# MaTouch_ESP32-S3_2_13_Quad-Color_Eink_V1.net
KiCad netlist of a schematic drawn in EAGLE
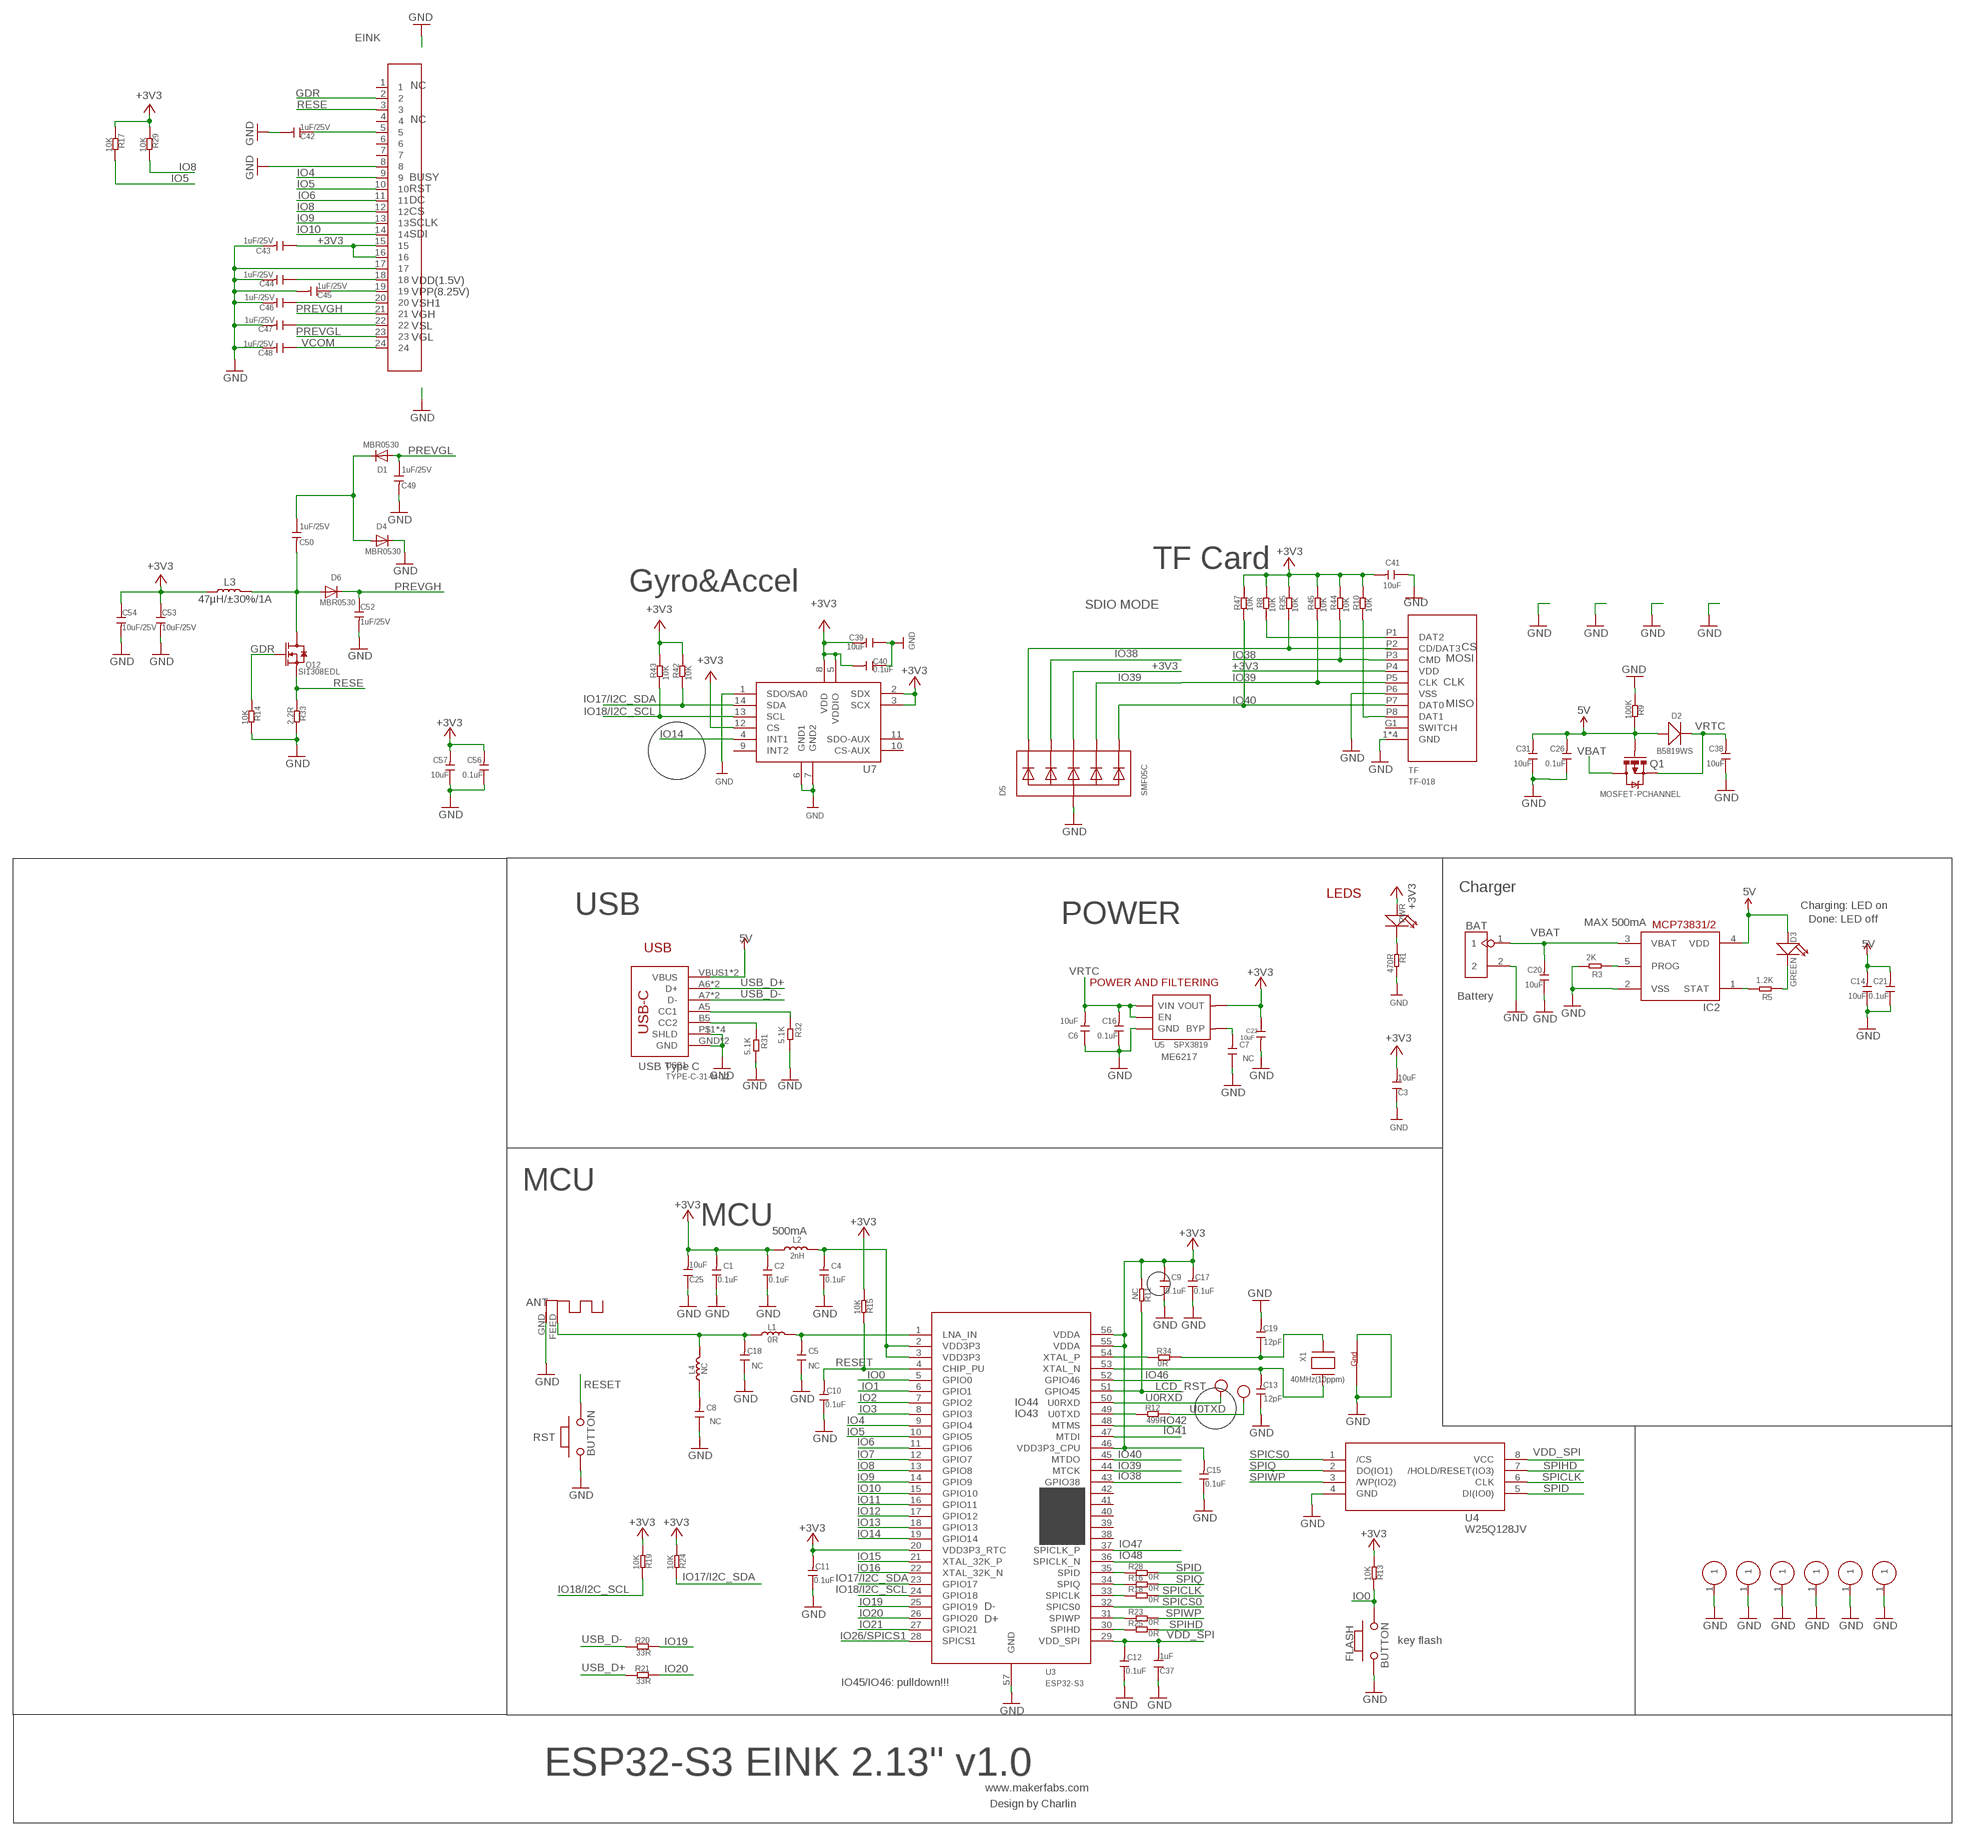
[diagram p0: schematic, sheet 1]

(export (version "E")
  (design (tool "Eeschema 10.0.6"))
  (components
    (comp (ref "ANT1")
      (value "ANTENNA")
      (footprint "eagle-import:RN-ANT")
      (libsource (lib "eagle-import") (part "ANTENNA"))
    )
    (comp (ref "BAT")
      (value "HEADER-2P-2.0")
      (footprint "eagle-import:2P-2.0")
      (libsource (lib "eagle-import") (part "HEADER-2P-2.0"))
    )
    (comp (ref "C1")
      (value "0.1uF")
      (footprint "eagle-import:DISCRETE_C0402")
      (libsource (lib "eagle-import") (part "DISCRETE_C-0402"))
    )
    (comp (ref "C2")
      (value "0.1uF")
      (footprint "eagle-import:DISCRETE_C0402")
      (libsource (lib "eagle-import") (part "DISCRETE_C-0402"))
    )
    (comp (ref "C3")
      (value "10uF")
      (footprint "eagle-import:DISCRETE_C0603")
      (libsource (lib "eagle-import") (part "DISCRETE_C-0603"))
    )
    (comp (ref "C4")
      (value "0.1uF")
      (footprint "eagle-import:DISCRETE_C0402")
      (libsource (lib "eagle-import") (part "DISCRETE_C-0402"))
    )
    (comp (ref "C5")
      (value "NC")
      (footprint "eagle-import:DISCRETE_C0402")
      (libsource (lib "eagle-import") (part "DISCRETE_C-0402"))
    )
    (comp (ref "C6")
      (value "10uF")
      (footprint "eagle-import:DISCRETE_C0603")
      (libsource (lib "eagle-import") (part "DISCRETE_C-0603"))
    )
    (comp (ref "C7")
      (value "NC")
      (footprint "eagle-import:DISCRETE_C0402")
      (libsource (lib "eagle-import") (part "DISCRETE_C-0402"))
    )
    (comp (ref "C8")
      (value "NC")
      (footprint "eagle-import:DISCRETE_C0402")
      (libsource (lib "eagle-import") (part "DISCRETE_C-0402"))
    )
    (comp (ref "C9")
      (value "0.1uF")
      (footprint "eagle-import:DISCRETE_C0402")
      (libsource (lib "eagle-import") (part "DISCRETE_C-0402"))
    )
    (comp (ref "C10")
      (value "0.1uF")
      (footprint "eagle-import:DISCRETE_C0402")
      (libsource (lib "eagle-import") (part "DISCRETE_C-0402"))
    )
    (comp (ref "C11")
      (value "0.1uF")
      (footprint "eagle-import:DISCRETE_C0402")
      (libsource (lib "eagle-import") (part "DISCRETE_C-0402"))
    )
    (comp (ref "C12")
      (value "0.1uF")
      (footprint "eagle-import:DISCRETE_C0402")
      (libsource (lib "eagle-import") (part "DISCRETE_C-0402"))
    )
    (comp (ref "C13")
      (value "12pF")
      (footprint "eagle-import:DISCRETE_C0402")
      (libsource (lib "eagle-import") (part "DISCRETE_C-0402"))
    )
    (comp (ref "C14")
      (value "10uF")
      (footprint "eagle-import:DISCRETE_C0402")
      (libsource (lib "eagle-import") (part "DISCRETE_C-0402"))
    )
    (comp (ref "C15")
      (value "0.1uF")
      (footprint "eagle-import:DISCRETE_C0402")
      (libsource (lib "eagle-import") (part "DISCRETE_C-0402"))
    )
    (comp (ref "C16")
      (value "0.1uF")
      (footprint "eagle-import:DISCRETE_C0402")
      (libsource (lib "eagle-import") (part "DISCRETE_C-0402"))
    )
    (comp (ref "C17")
      (value "0.1uF")
      (footprint "eagle-import:DISCRETE_C0402")
      (libsource (lib "eagle-import") (part "DISCRETE_C-0402"))
    )
    (comp (ref "C18")
      (value "NC")
      (footprint "eagle-import:DISCRETE_C0402")
      (libsource (lib "eagle-import") (part "DISCRETE_C-0402"))
    )
    (comp (ref "C19")
      (value "12pF")
      (footprint "eagle-import:DISCRETE_C0402")
      (libsource (lib "eagle-import") (part "DISCRETE_C-0402"))
    )
    (comp (ref "C20")
      (value "10uF")
      (footprint "eagle-import:DISCRETE_C0402")
      (libsource (lib "eagle-import") (part "DISCRETE_C-0402"))
    )
    (comp (ref "C21")
      (value "0.1uF")
      (footprint "eagle-import:DISCRETE_C0402")
      (libsource (lib "eagle-import") (part "DISCRETE_C-0402"))
    )
    (comp (ref "C22")
      (value "10uF")
      (footprint "eagle-import:0603")
      (libsource (lib "eagle-import") (part "C-0603"))
    )
    (comp (ref "C25")
      (value "10uF")
      (footprint "eagle-import:DISCRETE_C0603")
      (libsource (lib "eagle-import") (part "DISCRETE_C-0603"))
    )
    (comp (ref "C26")
      (value "0.1uF")
      (footprint "eagle-import:DISCRETE_C0402")
      (libsource (lib "eagle-import") (part "DISCRETE_C-0402"))
    )
    (comp (ref "C31")
      (value "10uF")
      (footprint "eagle-import:DISCRETE_C0402")
      (libsource (lib "eagle-import") (part "DISCRETE_C-0402"))
    )
    (comp (ref "C37")
      (value "1uF")
      (footprint "eagle-import:DISCRETE_C0603")
      (libsource (lib "eagle-import") (part "DISCRETE_C-0603"))
    )
    (comp (ref "C38")
      (value "10uF")
      (footprint "eagle-import:DISCRETE_C0402")
      (libsource (lib "eagle-import") (part "DISCRETE_C-0402"))
    )
    (comp (ref "C39")
      (value "10uF")
      (footprint "eagle-import:DISCRETE_C0402")
      (libsource (lib "eagle-import") (part "DISCRETE_C-0402"))
    )
    (comp (ref "C40")
      (value "0.1uF")
      (footprint "eagle-import:DISCRETE_C0402")
      (libsource (lib "eagle-import") (part "DISCRETE_C-0402"))
    )
    (comp (ref "C41")
      (value "10uF")
      (footprint "eagle-import:DISCRETE_C0402")
      (libsource (lib "eagle-import") (part "DISCRETE_C-0402"))
    )
    (comp (ref "C42")
      (value "1uF/25V")
      (footprint "eagle-import:DISCRETE_C0402")
      (libsource (lib "eagle-import") (part "DISCRETE_C-0402"))
    )
    (comp (ref "C43")
      (value "1uF/25V")
      (footprint "eagle-import:DISCRETE_C0402")
      (libsource (lib "eagle-import") (part "DISCRETE_C-0402"))
    )
    (comp (ref "C44")
      (value "1uF/25V")
      (footprint "eagle-import:DISCRETE_C0402")
      (libsource (lib "eagle-import") (part "DISCRETE_C-0402"))
    )
    (comp (ref "C45")
      (value "1uF/25V")
      (footprint "eagle-import:DISCRETE_C0402")
      (libsource (lib "eagle-import") (part "DISCRETE_C-0402"))
    )
    (comp (ref "C46")
      (value "1uF/25V")
      (footprint "eagle-import:DISCRETE_C0402")
      (libsource (lib "eagle-import") (part "DISCRETE_C-0402"))
    )
    (comp (ref "C47")
      (value "1uF/25V")
      (footprint "eagle-import:DISCRETE_C0402")
      (libsource (lib "eagle-import") (part "DISCRETE_C-0402"))
    )
    (comp (ref "C48")
      (value "1uF/25V")
      (footprint "eagle-import:DISCRETE_C0402")
      (libsource (lib "eagle-import") (part "DISCRETE_C-0402"))
    )
    (comp (ref "C49")
      (value "1uF/25V")
      (footprint "eagle-import:DISCRETE_C0402")
      (libsource (lib "eagle-import") (part "DISCRETE_C-0402"))
    )
    (comp (ref "C50")
      (value "1uF/25V")
      (footprint "eagle-import:DISCRETE_C0402")
      (libsource (lib "eagle-import") (part "DISCRETE_C-0402"))
    )
    (comp (ref "C52")
      (value "1uF/25V")
      (footprint "eagle-import:0603")
      (libsource (lib "eagle-import") (part "C-0603"))
    )
    (comp (ref "C53")
      (value "10uF/25V")
      (footprint "eagle-import:0603")
      (libsource (lib "eagle-import") (part "C-0603"))
    )
    (comp (ref "C54")
      (value "10uF/25V")
      (footprint "eagle-import:0603")
      (libsource (lib "eagle-import") (part "C-0603"))
    )
    (comp (ref "C56")
      (value "0.1uF")
      (footprint "eagle-import:DISCRETE_C0402")
      (libsource (lib "eagle-import") (part "DISCRETE_C-0402"))
    )
    (comp (ref "C57")
      (value "10uF")
      (footprint "eagle-import:DISCRETE_C0402")
      (libsource (lib "eagle-import") (part "DISCRETE_C-0402"))
    )
    (comp (ref "D1")
      (value "MBR0530")
      (footprint "eagle-import:SOD-323F")
      (libsource (lib "eagle-import") (part "DIODESOD-323F"))
    )
    (comp (ref "D2")
      (value "B5819WS")
      (footprint "eagle-import:SOD323")
      (libsource (lib "eagle-import") (part "D'0805'"))
    )
    (comp (ref "D3")
      (value "GREEN")
      (footprint "eagle-import:DISCRETE_LED-0603")
      (libsource (lib "eagle-import") (part "DISCRETE_LED0603"))
    )
    (comp (ref "D4")
      (value "MBR0530")
      (footprint "eagle-import:SOD-323F")
      (libsource (lib "eagle-import") (part "DIODESOD-323F"))
    )
    (comp (ref "D5")
      (value "SMF05C")
      (footprint "eagle-import:SOT363")
      (libsource (lib "eagle-import") (part "TVSARRAY_5LANE"))
    )
    (comp (ref "D6")
      (value "MBR0530")
      (footprint "eagle-import:SOD-323F")
      (libsource (lib "eagle-import") (part "DIODESOD-323F"))
    )
    (comp (ref "FLASH")
      (value "BUTTON")
      (footprint "eagle-import:157SW")
      (libsource (lib "eagle-import") (part "PB157"))
    )
    (comp (ref "IC2")
      (value "TP4054")
      (footprint "eagle-import:SOT23-5L")
      (libsource (lib "eagle-import") (part "MCP73831/OT"))
    )
    (comp (ref "J1")
      (value "FPC24-80P-A")
      (footprint "eagle-import:SMD24-80P-1960L440W")
      (libsource (lib "eagle-import") (part "FPC24-80P-A"))
    )
    (comp (ref "L1")
      (value "0R")
      (footprint "eagle-import:DISCRETE_L0402")
      (libsource (lib "eagle-import") (part "DISCRETE_L0402"))
    )
    (comp (ref "L2")
      (value "2nH")
      (footprint "eagle-import:DISCRETE_L0603")
      (libsource (lib "eagle-import") (part "DISCRETE_L0603"))
    )
    (comp (ref "L3")
      (value "47µH/±30%/1A")
      (footprint "eagle-import:CR54")
      (fields (field (name "PROD_ID") "NDUC-10789"))
      (libsource (lib "eagle-import") (part "INDUCTOR-CR54-47UH"))
    )
    (comp (ref "L4")
      (value "NC")
      (footprint "eagle-import:DISCRETE_L0402")
      (libsource (lib "eagle-import") (part "DISCRETE_L0402"))
    )
    (comp (ref "PWR")
      (value "DISCRETE_LED0603")
      (footprint "eagle-import:DISCRETE_LED-0603")
      (libsource (lib "eagle-import") (part "DISCRETE_LED0603"))
    )
    (comp (ref "Q1")
      (value "MOSFET-PCHANNEL")
      (footprint "eagle-import:SOT23-3")
      (libsource (lib "eagle-import") (part "MOSFET-PCHANNEL"))
    )
    (comp (ref "Q12")
      (value "SI1308EDL")
      (footprint "eagle-import:SOT23")
      (libsource (lib "eagle-import") (part "MOSFET-N'SOT23'"))
    )
    (comp (ref "R1")
      (value "470R")
      (footprint "eagle-import:DISCRETE_R0402")
      (libsource (lib "eagle-import") (part "DISCRETE_R-0402"))
    )
    (comp (ref "R3")
      (value "2K")
      (footprint "eagle-import:DISCRETE_R0402")
      (libsource (lib "eagle-import") (part "DISCRETE_R-0402"))
    )
    (comp (ref "R5")
      (value "1.2K")
      (footprint "eagle-import:DISCRETE_R0402")
      (libsource (lib "eagle-import") (part "DISCRETE_R-0402"))
    )
    (comp (ref "R8")
      (value "10K")
      (footprint "eagle-import:DISCRETE_R0402")
      (libsource (lib "eagle-import") (part "DISCRETE_R-0402"))
    )
    (comp (ref "R9")
      (value "100K")
      (footprint "eagle-import:DISCRETE_R0402")
      (libsource (lib "eagle-import") (part "DISCRETE_R-0402"))
    )
    (comp (ref "R10")
      (value "10K")
      (footprint "eagle-import:DISCRETE_R0402")
      (libsource (lib "eagle-import") (part "DISCRETE_R-0402"))
    )
    (comp (ref "R11")
      (value "NC")
      (footprint "eagle-import:DISCRETE_R0402")
      (libsource (lib "eagle-import") (part "DISCRETE_R-0402"))
    )
    (comp (ref "R12")
      (value "499R")
      (footprint "eagle-import:DISCRETE_R0402")
      (libsource (lib "eagle-import") (part "DISCRETE_R-0402"))
    )
    (comp (ref "R13")
      (value "10K")
      (footprint "eagle-import:DISCRETE_R0402")
      (libsource (lib "eagle-import") (part "DISCRETE_R-0402"))
    )
    (comp (ref "R14")
      (value "10K")
      (footprint "eagle-import:DISCRETE_R0402")
      (libsource (lib "eagle-import") (part "DISCRETE_R-0402"))
    )
    (comp (ref "R15")
      (value "10K")
      (footprint "eagle-import:DISCRETE_R0402")
      (libsource (lib "eagle-import") (part "DISCRETE_R-0402"))
    )
    (comp (ref "R16")
      (value "0R")
      (footprint "eagle-import:DISCRETE_R0402")
      (libsource (lib "eagle-import") (part "DISCRETE_R-0402"))
    )
    (comp (ref "R17")
      (value "10K")
      (footprint "eagle-import:DISCRETE_R0402")
      (libsource (lib "eagle-import") (part "DISCRETE_R-0402"))
    )
    (comp (ref "R18")
      (value "0R")
      (footprint "eagle-import:DISCRETE_R0402")
      (libsource (lib "eagle-import") (part "DISCRETE_R-0402"))
    )
    (comp (ref "R19")
      (value "10K")
      (footprint "eagle-import:DISCRETE_R0402")
      (libsource (lib "eagle-import") (part "DISCRETE_R-0402"))
    )
    (comp (ref "R20")
      (value "33R")
      (footprint "eagle-import:DISCRETE_R0402")
      (libsource (lib "eagle-import") (part "DISCRETE_R-0402"))
    )
    (comp (ref "R21")
      (value "33R")
      (footprint "eagle-import:DISCRETE_R0402")
      (libsource (lib "eagle-import") (part "DISCRETE_R-0402"))
    )
    (comp (ref "R23")
      (value "0R")
      (footprint "eagle-import:DISCRETE_R0402")
      (libsource (lib "eagle-import") (part "DISCRETE_R-0402"))
    )
    (comp (ref "R24")
      (value "10K")
      (footprint "eagle-import:DISCRETE_R0402")
      (libsource (lib "eagle-import") (part "DISCRETE_R-0402"))
    )
    (comp (ref "R25")
      (value "0R")
      (footprint "eagle-import:DISCRETE_R0402")
      (libsource (lib "eagle-import") (part "DISCRETE_R-0402"))
    )
    (comp (ref "R28")
      (value "0R")
      (footprint "eagle-import:DISCRETE_R0402")
      (libsource (lib "eagle-import") (part "DISCRETE_R-0402"))
    )
    (comp (ref "R29")
      (value "10K")
      (footprint "eagle-import:DISCRETE_R0402")
      (libsource (lib "eagle-import") (part "DISCRETE_R-0402"))
    )
    (comp (ref "R31")
      (value "5.1K")
      (footprint "eagle-import:DISCRETE_R0402")
      (libsource (lib "eagle-import") (part "DISCRETE_R-0402"))
    )
    (comp (ref "R32")
      (value "5.1K")
      (footprint "eagle-import:DISCRETE_R0402")
      (libsource (lib "eagle-import") (part "DISCRETE_R-0402"))
    )
    (comp (ref "R33")
      (value "2.2R")
      (footprint "eagle-import:DISCRETE_R0402")
      (libsource (lib "eagle-import") (part "DISCRETE_R-0402"))
    )
    (comp (ref "R34")
      (value "0R")
      (footprint "eagle-import:DISCRETE_R0402")
      (libsource (lib "eagle-import") (part "DISCRETE_R-0402"))
    )
    (comp (ref "R35")
      (value "10K")
      (footprint "eagle-import:DISCRETE_R0402")
      (libsource (lib "eagle-import") (part "DISCRETE_R-0402"))
    )
    (comp (ref "R42")
      (value "10K")
      (footprint "eagle-import:DISCRETE_R0402")
      (libsource (lib "eagle-import") (part "DISCRETE_R-0402"))
    )
    (comp (ref "R43")
      (value "10K")
      (footprint "eagle-import:DISCRETE_R0402")
      (libsource (lib "eagle-import") (part "DISCRETE_R-0402"))
    )
    (comp (ref "R44")
      (value "10K")
      (footprint "eagle-import:DISCRETE_R0402")
      (libsource (lib "eagle-import") (part "DISCRETE_R-0402"))
    )
    (comp (ref "R45")
      (value "10K")
      (footprint "eagle-import:DISCRETE_R0402")
      (libsource (lib "eagle-import") (part "DISCRETE_R-0402"))
    )
    (comp (ref "R47")
      (value "10K")
      (footprint "eagle-import:DISCRETE_R0402")
      (libsource (lib "eagle-import") (part "DISCRETE_R-0402"))
    )
    (comp (ref "RST")
      (value "BUTTON")
      (footprint "eagle-import:157SW")
      (libsource (lib "eagle-import") (part "PB157"))
    )
    (comp (ref "RX")
      (value "TEST-POINT'4545'")
      (footprint "eagle-import:TP-D45MIL")
      (fields (field (name "PARTNO") "DNP") (field (name "PARTNO_1") "DNP"))
      (libsource (lib "eagle-import") (part "TEST-POINT'4545'"))
    )
    (comp (ref "S1")
      (value "ONEPIN01")
      (footprint "eagle-import:ONEPIN01")
      (libsource (lib "eagle-import") (part "ONEPIN01"))
    )
    (comp (ref "S2")
      (value "ONEPIN01")
      (footprint "eagle-import:ONEPIN01")
      (libsource (lib "eagle-import") (part "ONEPIN01"))
    )
    (comp (ref "S3")
      (value "ONEPIN01")
      (footprint "eagle-import:ONEPIN01")
      (libsource (lib "eagle-import") (part "ONEPIN01"))
    )
    (comp (ref "S4")
      (value "ONEPIN01")
      (footprint "eagle-import:ONEPIN01")
      (libsource (lib "eagle-import") (part "ONEPIN01"))
    )
    (comp (ref "S5")
      (value "ONEPIN01")
      (footprint "eagle-import:ONEPIN01")
      (libsource (lib "eagle-import") (part "ONEPIN01"))
    )
    (comp (ref "S6")
      (value "ONEPIN01")
      (footprint "eagle-import:ONEPIN01")
      (libsource (lib "eagle-import") (part "ONEPIN01"))
    )
    (comp (ref "TF")
      (value "TF-018")
      (footprint "eagle-import:TF-018")
      (libsource (lib "eagle-import") (part "TF-018"))
    )
    (comp (ref "TX")
      (value "TEST-POINT'4545'")
      (footprint "eagle-import:TP-D45MIL")
      (fields (field (name "PARTNO") "DNP") (field (name "PARTNO_1") "DNP"))
      (libsource (lib "eagle-import") (part "TEST-POINT'4545'"))
    )
    (comp (ref "U3")
      (value "ESP32-S3")
      (footprint "eagle-import:QFN56-7_7MM")
      (libsource (lib "eagle-import") (part "ESP32-S3"))
    )
    (comp (ref "U4")
      (value "W25Q128JV")
      (footprint "eagle-import:SOIC-8-208MIL")
      (libsource (lib "eagle-import") (part "W25Q128JV"))
    )
    (comp (ref "U5")
      (value "SPX3819")
      (footprint "eagle-import:SOT23-5")
      (libsource (lib "eagle-import") (part "SPX3819"))
    )
    (comp (ref "U7")
      (value "QMI8658A")
      (footprint "eagle-import:LGA14-50P-300L250W86H")
      (libsource (lib "eagle-import") (part "QMI8658A"))
    )
    (comp (ref "USB1")
      (value "TYPE-C-31-M-12")
      (footprint "eagle-import:TYPE-C-31-M-12")
      (libsource (lib "eagle-import") (part "TYPE-C-31-M-12"))
    )
    (comp (ref "X1")
      (value "40MHz(10ppm)")
      (footprint "eagle-import:NX3225")
      (libsource (lib "eagle-import") (part "XTAL-4-3225"))
    )
  )
  (nets
    (net (code "1") (name "+3V3") (class "Default")
      (node (ref "C1") (pin "2") (pinfunction "2_2") (pintype "passive"))
      (node (ref "C11") (pin "2") (pinfunction "2_2") (pintype "passive"))
      (node (ref "C15") (pin "2") (pinfunction "2_2") (pintype "passive"))
      (node (ref "C17") (pin "2") (pinfunction "2_2") (pintype "passive"))
      (node (ref "C2") (pin "2") (pinfunction "2_2") (pintype "passive"))
      (node (ref "C22") (pin "1") (pinfunction "1_1") (pintype "passive"))
      (node (ref "C25") (pin "2") (pinfunction "2_2") (pintype "passive"))
      (node (ref "C3") (pin "2") (pinfunction "2_2") (pintype "passive"))
      (node (ref "C39") (pin "2") (pinfunction "2_2") (pintype "passive"))
      (node (ref "C40") (pin "2") (pinfunction "2_2") (pintype "passive"))
      (node (ref "C41") (pin "2") (pinfunction "2_2") (pintype "passive"))
      (node (ref "C43") (pin "1") (pinfunction "1_1") (pintype "passive"))
      (node (ref "C53") (pin "1") (pinfunction "1_1") (pintype "passive"))
      (node (ref "C54") (pin "1") (pinfunction "1_1") (pintype "passive"))
      (node (ref "C56") (pin "2") (pinfunction "2_2") (pintype "passive"))
      (node (ref "C57") (pin "2") (pinfunction "2_2") (pintype "passive"))
      (node (ref "C9") (pin "2") (pinfunction "2_2") (pintype "passive"))
      (node (ref "D5") (pin "4") (pinfunction "C3_4") (pintype "passive"))
      (node (ref "J1") (pin "15") (pinfunction "15_15") (pintype "bidirectional"))
      (node (ref "J1") (pin "16") (pinfunction "16_16") (pintype "bidirectional"))
      (node (ref "L2") (pin "1") (pinfunction "1_1") (pintype "passive"))
      (node (ref "L3") (pin "P$1") (pinfunction "1_P$1") (pintype "passive"))
      (node (ref "PWR") (pin "+") (pinfunction "+_+") (pintype "passive"))
      (node (ref "R10") (pin "2") (pinfunction "2_2") (pintype "passive"))
      (node (ref "R11") (pin "2") (pinfunction "2_2") (pintype "passive"))
      (node (ref "R13") (pin "2") (pinfunction "2_2") (pintype "passive"))
      (node (ref "R15") (pin "2") (pinfunction "2_2") (pintype "passive"))
      (node (ref "R17") (pin "1") (pinfunction "1_1") (pintype "passive"))
      (node (ref "R19") (pin "2") (pinfunction "2_2") (pintype "passive"))
      (node (ref "R24") (pin "2") (pinfunction "2_2") (pintype "passive"))
      (node (ref "R29") (pin "1") (pinfunction "1_1") (pintype "passive"))
      (node (ref "R35") (pin "2") (pinfunction "2_2") (pintype "passive"))
      (node (ref "R42") (pin "2") (pinfunction "2_2") (pintype "passive"))
      (node (ref "R43") (pin "2") (pinfunction "2_2") (pintype "passive"))
      (node (ref "R44") (pin "2") (pinfunction "2_2") (pintype "passive"))
      (node (ref "R45") (pin "2") (pinfunction "2_2") (pintype "passive"))
      (node (ref "R47") (pin "2") (pinfunction "2_2") (pintype "passive"))
      (node (ref "R8") (pin "2") (pinfunction "2_2") (pintype "passive"))
      (node (ref "TF") (pin "P4") (pinfunction "VDD_P4") (pintype "bidirectional"))
      (node (ref "U3") (pin "20") (pinfunction "VDD3P3_RTC_20") (pintype "bidirectional"))
      (node (ref "U3") (pin "46") (pinfunction "VDD3P3_CPU_46") (pintype "bidirectional"))
      (node (ref "U3") (pin "55") (pinfunction "VDDA_55") (pintype "bidirectional"))
      (node (ref "U3") (pin "56") (pinfunction "VDDA_56") (pintype "bidirectional"))
      (node (ref "U5") (pin "5") (pinfunction "VOUT_5") (pintype "bidirectional"))
      (node (ref "U7") (pin "12") (pinfunction "CS_12") (pintype "bidirectional"))
      (node (ref "U7") (pin "2") (pinfunction "SDX_2") (pintype "bidirectional"))
      (node (ref "U7") (pin "3") (pinfunction "SCX_3") (pintype "bidirectional"))
      (node (ref "U7") (pin "5") (pinfunction "VDDIO_5") (pintype "bidirectional"))
      (node (ref "U7") (pin "8") (pinfunction "VDD_8") (pintype "bidirectional"))
    )
    (net (code "2") (name "/GDR") (class "Default")
      (node (ref "J1") (pin "2") (pinfunction "2_2") (pintype "bidirectional"))
      (node (ref "Q12") (pin "1") (pinfunction "G_1") (pintype "passive"))
      (node (ref "R14") (pin "1") (pinfunction "1_1") (pintype "passive"))
    )
    (net (code "3") (name "/IO0") (class "Default")
      (node (ref "FLASH") (pin "2") (pinfunction "2_2") (pintype "passive"))
      (node (ref "R13") (pin "1") (pinfunction "1_1") (pintype "passive"))
      (node (ref "U3") (pin "5") (pinfunction "GPIO0_5") (pintype "bidirectional"))
    )
    (net (code "4") (name "/IO1") (class "Default")
      (node (ref "U3") (pin "6") (pinfunction "GPIO1_6") (pintype "bidirectional"))
    )
    (net (code "5") (name "/IO2") (class "Default")
      (node (ref "U3") (pin "7") (pinfunction "GPIO2_7") (pintype "bidirectional"))
    )
    (net (code "6") (name "/IO3") (class "Default")
      (node (ref "U3") (pin "8") (pinfunction "GPIO3_8") (pintype "bidirectional"))
    )
    (net (code "7") (name "/IO4") (class "Default")
      (node (ref "J1") (pin "9") (pinfunction "9_9") (pintype "bidirectional"))
      (node (ref "U3") (pin "9") (pinfunction "GPIO4_9") (pintype "bidirectional"))
    )
    (net (code "8") (name "/IO5") (class "Default")
      (node (ref "J1") (pin "10") (pinfunction "10_10") (pintype "bidirectional"))
      (node (ref "R17") (pin "2") (pinfunction "2_2") (pintype "passive"))
      (node (ref "U3") (pin "10") (pinfunction "GPIO5_10") (pintype "bidirectional"))
    )
    (net (code "9") (name "/IO6") (class "Default")
      (node (ref "J1") (pin "11") (pinfunction "11_11") (pintype "bidirectional"))
      (node (ref "U3") (pin "11") (pinfunction "GPIO6_11") (pintype "bidirectional"))
    )
    (net (code "10") (name "/IO7") (class "Default")
      (node (ref "U3") (pin "12") (pinfunction "GPIO7_12") (pintype "bidirectional"))
    )
    (net (code "11") (name "/IO8") (class "Default")
      (node (ref "J1") (pin "12") (pinfunction "12_12") (pintype "bidirectional"))
      (node (ref "R29") (pin "2") (pinfunction "2_2") (pintype "passive"))
      (node (ref "U3") (pin "13") (pinfunction "GPIO8_13") (pintype "bidirectional"))
    )
    (net (code "12") (name "/IO9") (class "Default")
      (node (ref "J1") (pin "13") (pinfunction "13_13") (pintype "bidirectional"))
      (node (ref "U3") (pin "14") (pinfunction "GPIO9_14") (pintype "bidirectional"))
    )
    (net (code "13") (name "/IO10") (class "Default")
      (node (ref "J1") (pin "14") (pinfunction "14_14") (pintype "bidirectional"))
      (node (ref "U3") (pin "15") (pinfunction "GPIO10_15") (pintype "bidirectional"))
    )
    (net (code "14") (name "/IO11") (class "Default")
      (node (ref "U3") (pin "16") (pinfunction "GPIO11_16") (pintype "bidirectional"))
    )
    (net (code "15") (name "/IO12") (class "Default")
      (node (ref "U3") (pin "17") (pinfunction "GPIO12_17") (pintype "bidirectional"))
    )
    (net (code "16") (name "/IO13") (class "Default")
      (node (ref "U3") (pin "18") (pinfunction "GPIO13_18") (pintype "bidirectional"))
    )
    (net (code "17") (name "/IO14") (class "Default")
      (node (ref "U3") (pin "19") (pinfunction "GPIO14_19") (pintype "bidirectional"))
      (node (ref "U7") (pin "4") (pinfunction "INT1_4") (pintype "bidirectional"))
    )
    (net (code "18") (name "/IO15") (class "Default")
      (node (ref "U3") (pin "21") (pinfunction "XTAL_32K_P_21") (pintype "bidirectional"))
    )
    (net (code "19") (name "/IO16") (class "Default")
      (node (ref "U3") (pin "22") (pinfunction "XTAL_32K_N_22") (pintype "bidirectional"))
    )
    (net (code "20") (name "/IO17{slash}I2C_SDA") (class "Default")
      (node (ref "R24") (pin "1") (pinfunction "1_1") (pintype "passive"))
      (node (ref "R42") (pin "1") (pinfunction "1_1") (pintype "passive"))
      (node (ref "U3") (pin "23") (pinfunction "GPIO17_23") (pintype "bidirectional"))
      (node (ref "U7") (pin "14") (pinfunction "SDA_14") (pintype "bidirectional"))
    )
    (net (code "21") (name "/IO18{slash}I2C_SCL") (class "Default")
      (node (ref "R19") (pin "1") (pinfunction "1_1") (pintype "passive"))
      (node (ref "R43") (pin "1") (pinfunction "1_1") (pintype "passive"))
      (node (ref "U3") (pin "24") (pinfunction "GPIO18_24") (pintype "bidirectional"))
      (node (ref "U7") (pin "13") (pinfunction "SCL_13") (pintype "bidirectional"))
    )
    (net (code "22") (name "/IO19") (class "Default")
      (node (ref "R20") (pin "1") (pinfunction "1_1") (pintype "passive"))
      (node (ref "U3") (pin "25") (pinfunction "GPIO19_25") (pintype "bidirectional"))
    )
    (net (code "23") (name "/IO20") (class "Default")
      (node (ref "R21") (pin "1") (pinfunction "1_1") (pintype "passive"))
      (node (ref "U3") (pin "26") (pinfunction "GPIO20_26") (pintype "bidirectional"))
    )
    (net (code "24") (name "/IO21") (class "Default")
      (node (ref "U3") (pin "27") (pinfunction "GPIO21_27") (pintype "bidirectional"))
    )
    (net (code "25") (name "/IO26{slash}SPICS1") (class "Default")
      (node (ref "U3") (pin "28") (pinfunction "SPICS1_28") (pintype "bidirectional"))
    )
    (net (code "26") (name "/IO38") (class "Default")
      (node (ref "D5") (pin "3") (pinfunction "C2_3") (pintype "passive"))
      (node (ref "R44") (pin "1") (pinfunction "1_1") (pintype "passive"))
      (node (ref "TF") (pin "P3") (pinfunction "CMD_P3") (pintype "bidirectional"))
      (node (ref "U3") (pin "43") (pinfunction "GPIO38_43") (pintype "bidirectional"))
    )
    (net (code "27") (name "/IO39") (class "Default")
      (node (ref "D5") (pin "5") (pinfunction "C4_5") (pintype "passive"))
      (node (ref "R45") (pin "1") (pinfunction "1_1") (pintype "passive"))
      (node (ref "TF") (pin "P5") (pinfunction "CLK_P5") (pintype "bidirectional"))
      (node (ref "U3") (pin "44") (pinfunction "MTCK_44") (pintype "bidirectional"))
    )
    (net (code "28") (name "/IO40") (class "Default")
      (node (ref "D5") (pin "6") (pinfunction "C5_6") (pintype "passive"))
      (node (ref "R47") (pin "1") (pinfunction "1_1") (pintype "passive"))
      (node (ref "TF") (pin "P7") (pinfunction "DAT0_P7") (pintype "bidirectional"))
      (node (ref "U3") (pin "45") (pinfunction "MTDO_45") (pintype "bidirectional"))
    )
    (net (code "29") (name "/IO41") (class "Default")
      (node (ref "U3") (pin "47") (pinfunction "MTDI_47") (pintype "bidirectional"))
    )
    (net (code "30") (name "/IO42") (class "Default")
      (node (ref "U3") (pin "48") (pinfunction "MTMS_48") (pintype "bidirectional"))
    )
    (net (code "31") (name "/IO46") (class "Default")
      (node (ref "U3") (pin "52") (pinfunction "GPIO46_52") (pintype "bidirectional"))
    )
    (net (code "32") (name "/IO47") (class "Default")
      (node (ref "U3") (pin "37") (pinfunction "SPICLK_P_37") (pintype "bidirectional"))
    )
    (net (code "33") (name "/IO48") (class "Default")
      (node (ref "U3") (pin "36") (pinfunction "SPICLK_N_36") (pintype "bidirectional"))
    )
    (net (code "34") (name "/LCD_RST") (class "Default")
      (node (ref "R11") (pin "1") (pinfunction "1_1") (pintype "passive"))
      (node (ref "U3") (pin "51") (pinfunction "GPIO45_51") (pintype "bidirectional"))
    )
    (net (code "35") (name "/PREVGH") (class "Default")
      (node (ref "C52") (pin "1") (pinfunction "1_1") (pintype "passive"))
      (node (ref "D6") (pin "C") (pinfunction "C_C") (pintype "passive"))
      (node (ref "J1") (pin "21") (pinfunction "21_21") (pintype "bidirectional"))
    )
    (net (code "36") (name "/PREVGL") (class "Default")
      (node (ref "C49") (pin "1") (pinfunction "1_1") (pintype "passive"))
      (node (ref "D1") (pin "A") (pinfunction "A_A") (pintype "passive"))
      (node (ref "J1") (pin "23") (pinfunction "23_23") (pintype "bidirectional"))
    )
    (net (code "37") (name "/RESE") (class "Default")
      (node (ref "J1") (pin "3") (pinfunction "3_3") (pintype "bidirectional"))
      (node (ref "Q12") (pin "2") (pinfunction "S_2") (pintype "passive"))
      (node (ref "R33") (pin "1") (pinfunction "1_1") (pintype "passive"))
    )
    (net (code "38") (name "/RESET") (class "Default")
      (node (ref "C10") (pin "2") (pinfunction "2_2") (pintype "passive"))
      (node (ref "R15") (pin "1") (pinfunction "1_1") (pintype "passive"))
      (node (ref "RST") (pin "2") (pinfunction "2_2") (pintype "passive"))
      (node (ref "U3") (pin "4") (pinfunction "CHIP_PU_4") (pintype "bidirectional"))
    )
    (net (code "39") (name "/SPICLK") (class "Default")
      (node (ref "R18") (pin "1") (pinfunction "1_1") (pintype "passive"))
      (node (ref "U4") (pin "6") (pinfunction "CLK_6") (pintype "bidirectional"))
    )
    (net (code "40") (name "/SPICS0") (class "Default")
      (node (ref "U3") (pin "32") (pinfunction "SPICS0_32") (pintype "bidirectional"))
      (node (ref "U4") (pin "1") (pinfunction "/CS_1") (pintype "bidirectional"))
    )
    (net (code "41") (name "/SPID") (class "Default")
      (node (ref "R28") (pin "1") (pinfunction "1_1") (pintype "passive"))
      (node (ref "U4") (pin "5") (pinfunction "DI(IO0)_5") (pintype "bidirectional"))
    )
    (net (code "42") (name "/SPIHD") (class "Default")
      (node (ref "R25") (pin "1") (pinfunction "1_1") (pintype "passive"))
      (node (ref "U4") (pin "7") (pinfunction "/HOLD/RESET(IO3)_7") (pintype "bidirectional"))
    )
    (net (code "43") (name "/SPIQ") (class "Default")
      (node (ref "R16") (pin "1") (pinfunction "1_1") (pintype "passive"))
      (node (ref "U4") (pin "2") (pinfunction "DO(IO1)_2") (pintype "bidirectional"))
    )
    (net (code "44") (name "/SPIWP") (class "Default")
      (node (ref "R23") (pin "1") (pinfunction "1_1") (pintype "passive"))
      (node (ref "U4") (pin "3") (pinfunction "/WP(IO2)_3") (pintype "bidirectional"))
    )
    (net (code "45") (name "/U0RXD") (class "Default")
      (node (ref "RX") (pin "T") (pinfunction "T_T") (pintype "bidirectional"))
      (node (ref "U3") (pin "50") (pinfunction "U0RXD_50") (pintype "bidirectional"))
    )
    (net (code "46") (name "/U0TXD") (class "Default")
      (node (ref "R12") (pin "1") (pinfunction "1_1") (pintype "passive"))
      (node (ref "TX") (pin "T") (pinfunction "T_T") (pintype "bidirectional"))
    )
    (net (code "47") (name "/USB_D+") (class "Default")
      (node (ref "R21") (pin "2") (pinfunction "2_2") (pintype "passive"))
      (node (ref "USB1") (pin "A6") (pinfunction "D+_A6") (pintype "bidirectional"))
      (node (ref "USB1") (pin "B6") (pinfunction "D+_B6") (pintype "bidirectional"))
    )
    (net (code "48") (name "/USB_D-") (class "Default")
      (node (ref "R20") (pin "2") (pinfunction "2_2") (pintype "passive"))
      (node (ref "USB1") (pin "A7") (pinfunction "D-_A7") (pintype "bidirectional"))
      (node (ref "USB1") (pin "B7") (pinfunction "D-_B7") (pintype "bidirectional"))
    )
    (net (code "49") (name "/VBAT") (class "Default")
      (node (ref "BAT") (pin "1") (pinfunction "1_1") (pintype "bidirectional"))
      (node (ref "C20") (pin "2") (pinfunction "2_2") (pintype "passive"))
      (node (ref "IC2") (pin "3") (pinfunction "VBAT_3") (pintype "bidirectional"))
      (node (ref "Q1") (pin "3") (pinfunction "D_3") (pintype "passive"))
    )
    (net (code "50") (name "/VCOM") (class "Default")
      (node (ref "C48") (pin "1") (pinfunction "1_1") (pintype "passive"))
      (node (ref "J1") (pin "24") (pinfunction "24_24") (pintype "bidirectional"))
    )
    (net (code "51") (name "/VDD_SPI") (class "Default")
      (node (ref "C12") (pin "2") (pinfunction "2_2") (pintype "passive"))
      (node (ref "C37") (pin "2") (pinfunction "2_2") (pintype "passive"))
      (node (ref "U3") (pin "29") (pinfunction "VDD_SPI_29") (pintype "bidirectional"))
      (node (ref "U4") (pin "8") (pinfunction "VCC_8") (pintype "bidirectional"))
    )
    (net (code "52") (name "/VRTC") (class "Default")
      (node (ref "C16") (pin "2") (pinfunction "2_2") (pintype "passive"))
      (node (ref "C38") (pin "2") (pinfunction "2_2") (pintype "passive"))
      (node (ref "C6") (pin "2") (pinfunction "2_2") (pintype "passive"))
      (node (ref "D2") (pin "-") (pinfunction "-_-") (pintype "passive"))
      (node (ref "Q1") (pin "2") (pinfunction "S_2") (pintype "passive"))
      (node (ref "U5") (pin "1") (pinfunction "VIN_1") (pintype "bidirectional"))
      (node (ref "U5") (pin "3") (pinfunction "EN_3") (pintype "bidirectional"))
    )
    (net (code "53") (name "5V") (class "Default")
      (node (ref "C14") (pin "2") (pinfunction "2_2") (pintype "passive"))
      (node (ref "C21") (pin "2") (pinfunction "2_2") (pintype "passive"))
      (node (ref "C26") (pin "2") (pinfunction "2_2") (pintype "passive"))
      (node (ref "C31") (pin "2") (pinfunction "2_2") (pintype "passive"))
      (node (ref "D2") (pin "+") (pinfunction "+_+") (pintype "passive"))
      (node (ref "D3") (pin "+") (pinfunction "+_+") (pintype "passive"))
      (node (ref "IC2") (pin "4") (pinfunction "VDD_4") (pintype "power_in"))
      (node (ref "Q1") (pin "1") (pinfunction "G_1") (pintype "passive"))
      (node (ref "R9") (pin "2") (pinfunction "2_2") (pintype "passive"))
      (node (ref "USB1") (pin "VBUS1") (pinfunction "VBUS_VBUS1") (pintype "bidirectional"))
      (node (ref "USB1") (pin "VBUS2") (pinfunction "VBUS_VBUS2") (pintype "bidirectional"))
    )
    (net (code "54") (name "GND") (class "Default")
      (node (ref "ANT1") (pin "GND") (pinfunction "GND_GND") (pintype "passive"))
      (node (ref "BAT") (pin "2") (pinfunction "2_2") (pintype "bidirectional"))
      (node (ref "C1") (pin "1") (pinfunction "1_1") (pintype "passive"))
      (node (ref "C10") (pin "1") (pinfunction "1_1") (pintype "passive"))
      (node (ref "C11") (pin "1") (pinfunction "1_1") (pintype "passive"))
      (node (ref "C12") (pin "1") (pinfunction "1_1") (pintype "passive"))
      (node (ref "C13") (pin "1") (pinfunction "1_1") (pintype "passive"))
      (node (ref "C14") (pin "1") (pinfunction "1_1") (pintype "passive"))
      (node (ref "C15") (pin "1") (pinfunction "1_1") (pintype "passive"))
      (node (ref "C16") (pin "1") (pinfunction "1_1") (pintype "passive"))
      (node (ref "C17") (pin "1") (pinfunction "1_1") (pintype "passive"))
      (node (ref "C18") (pin "1") (pinfunction "1_1") (pintype "passive"))
      (node (ref "C19") (pin "2") (pinfunction "2_2") (pintype "passive"))
      (node (ref "C2") (pin "1") (pinfunction "1_1") (pintype "passive"))
      (node (ref "C20") (pin "1") (pinfunction "1_1") (pintype "passive"))
      (node (ref "C21") (pin "1") (pinfunction "1_1") (pintype "passive"))
      (node (ref "C22") (pin "2") (pinfunction "2_2") (pintype "passive"))
      (node (ref "C25") (pin "1") (pinfunction "1_1") (pintype "passive"))
      (node (ref "C26") (pin "1") (pinfunction "1_1") (pintype "passive"))
      (node (ref "C3") (pin "1") (pinfunction "1_1") (pintype "passive"))
      (node (ref "C31") (pin "1") (pinfunction "1_1") (pintype "passive"))
      (node (ref "C37") (pin "1") (pinfunction "1_1") (pintype "passive"))
      (node (ref "C38") (pin "1") (pinfunction "1_1") (pintype "passive"))
      (node (ref "C39") (pin "1") (pinfunction "1_1") (pintype "passive"))
      (node (ref "C4") (pin "1") (pinfunction "1_1") (pintype "passive"))
      (node (ref "C40") (pin "1") (pinfunction "1_1") (pintype "passive"))
      (node (ref "C41") (pin "1") (pinfunction "1_1") (pintype "passive"))
      (node (ref "C42") (pin "2") (pinfunction "2_2") (pintype "passive"))
      (node (ref "C43") (pin "2") (pinfunction "2_2") (pintype "passive"))
      (node (ref "C44") (pin "2") (pinfunction "2_2") (pintype "passive"))
      (node (ref "C45") (pin "2") (pinfunction "2_2") (pintype "passive"))
      (node (ref "C46") (pin "2") (pinfunction "2_2") (pintype "passive"))
      (node (ref "C47") (pin "2") (pinfunction "2_2") (pintype "passive"))
      (node (ref "C48") (pin "2") (pinfunction "2_2") (pintype "passive"))
      (node (ref "C49") (pin "2") (pinfunction "2_2") (pintype "passive"))
      (node (ref "C5") (pin "1") (pinfunction "1_1") (pintype "passive"))
      (node (ref "C52") (pin "2") (pinfunction "2_2") (pintype "passive"))
      (node (ref "C53") (pin "2") (pinfunction "2_2") (pintype "passive"))
      (node (ref "C54") (pin "2") (pinfunction "2_2") (pintype "passive"))
      (node (ref "C56") (pin "1") (pinfunction "1_1") (pintype "passive"))
      (node (ref "C57") (pin "1") (pinfunction "1_1") (pintype "passive"))
      (node (ref "C6") (pin "1") (pinfunction "1_1") (pintype "passive"))
      (node (ref "C7") (pin "1") (pinfunction "1_1") (pintype "passive"))
      (node (ref "C8") (pin "1") (pinfunction "1_1") (pintype "passive"))
      (node (ref "C9") (pin "1") (pinfunction "1_1") (pintype "passive"))
      (node (ref "D4") (pin "C") (pinfunction "C_C") (pintype "passive"))
      (node (ref "D5") (pin "2") (pinfunction "A_2") (pintype "passive"))
      (node (ref "FLASH") (pin "1") (pinfunction "1_1") (pintype "passive"))
      (node (ref "IC2") (pin "2") (pinfunction "VSS_2") (pintype "power_in"))
      (node (ref "J1") (pin "17") (pinfunction "17_17") (pintype "bidirectional"))
      (node (ref "J1") (pin "8") (pinfunction "8_8") (pintype "bidirectional"))
      (node (ref "R1") (pin "1") (pinfunction "1_1") (pintype "passive"))
      (node (ref "R14") (pin "2") (pinfunction "2_2") (pintype "passive"))
      (node (ref "R3") (pin "2") (pinfunction "2_2") (pintype "passive"))
      (node (ref "R31") (pin "2") (pinfunction "2_2") (pintype "passive"))
      (node (ref "R32") (pin "2") (pinfunction "2_2") (pintype "passive"))
      (node (ref "R33") (pin "2") (pinfunction "2_2") (pintype "passive"))
      (node (ref "R9") (pin "1") (pinfunction "1_1") (pintype "passive"))
      (node (ref "RST") (pin "1") (pinfunction "1_1") (pintype "passive"))
      (node (ref "S1") (pin "1") (pinfunction "1_1") (pintype "bidirectional"))
      (node (ref "S2") (pin "1") (pinfunction "1_1") (pintype "bidirectional"))
      (node (ref "S3") (pin "1") (pinfunction "1_1") (pintype "bidirectional"))
      (node (ref "S4") (pin "1") (pinfunction "1_1") (pintype "bidirectional"))
      (node (ref "S5") (pin "1") (pinfunction "1_1") (pintype "bidirectional"))
      (node (ref "S6") (pin "1") (pinfunction "1_1") (pintype "bidirectional"))
      (node (ref "TF") (pin "1") (pinfunction "GND_1") (pintype "bidirectional"))
      (node (ref "TF") (pin "2") (pinfunction "GND_2") (pintype "bidirectional"))
      (node (ref "TF") (pin "3") (pinfunction "GND_3") (pintype "bidirectional"))
      (node (ref "TF") (pin "4") (pinfunction "GND_4") (pintype "bidirectional"))
      (node (ref "TF") (pin "P6") (pinfunction "VSS_P6") (pintype "bidirectional"))
      (node (ref "U3") (pin "57") (pinfunction "GND_57") (pintype "bidirectional"))
      (node (ref "U4") (pin "4") (pinfunction "GND_4") (pintype "bidirectional"))
      (node (ref "U5") (pin "2") (pinfunction "GND_2") (pintype "bidirectional"))
      (node (ref "U7") (pin "1") (pinfunction "SDO/SA0_1") (pintype "bidirectional"))
      (node (ref "U7") (pin "6") (pinfunction "GND1_6") (pintype "bidirectional"))
      (node (ref "U7") (pin "7") (pinfunction "GND2_7") (pintype "bidirectional"))
      (node (ref "USB1") (pin "GND") (pinfunction "GND_GND") (pintype "bidirectional"))
      (node (ref "USB1") (pin "GND2") (pinfunction "GND_GND2") (pintype "bidirectional"))
      (node (ref "USB1") (pin "P$1") (pinfunction "SHLD_P$1") (pintype "bidirectional"))
      (node (ref "USB1") (pin "P$2") (pinfunction "SHLD_P$2") (pintype "bidirectional"))
      (node (ref "USB1") (pin "P$3") (pinfunction "SHLD_P$3") (pintype "bidirectional"))
      (node (ref "USB1") (pin "P$4") (pinfunction "SHLD_P$4") (pintype "bidirectional"))
      (node (ref "X1") (pin "2") (pinfunction "G2_2") (pintype "power_in"))
      (node (ref "X1") (pin "4") (pinfunction "G1_4") (pintype "power_in"))
    )
    (net (code "55") (name "Net-(ANT1-PadFEED)") (class "Default")
      (node (ref "ANT1") (pin "FEED") (pinfunction "FEED_FEED") (pintype "passive"))
      (node (ref "C18") (pin "2") (pinfunction "2_2") (pintype "passive"))
      (node (ref "L1") (pin "1") (pinfunction "1_1") (pintype "passive"))
      (node (ref "L4") (pin "2") (pinfunction "2_2") (pintype "passive"))
    )
    (net (code "56") (name "Net-(C4-Pad2)") (class "Default")
      (node (ref "C4") (pin "2") (pinfunction "2_2") (pintype "passive"))
      (node (ref "L2") (pin "2") (pinfunction "2_2") (pintype "passive"))
      (node (ref "U3") (pin "2") (pinfunction "VDD3P3_2") (pintype "bidirectional"))
      (node (ref "U3") (pin "3") (pinfunction "VDD3P3_3") (pintype "bidirectional"))
    )
    (net (code "57") (name "Net-(C8-Pad2)") (class "Default")
      (node (ref "C8") (pin "2") (pinfunction "2_2") (pintype "passive"))
      (node (ref "L4") (pin "1") (pinfunction "1_1") (pintype "passive"))
    )
    (net (code "58") (name "Net-(C42-Pad1)") (class "Default")
      (node (ref "C42") (pin "1") (pinfunction "1_1") (pintype "passive"))
      (node (ref "J1") (pin "5") (pinfunction "5_5") (pintype "bidirectional"))
    )
    (net (code "59") (name "Net-(C44-Pad1)") (class "Default")
      (node (ref "C44") (pin "1") (pinfunction "1_1") (pintype "passive"))
      (node (ref "J1") (pin "18") (pinfunction "18_18") (pintype "bidirectional"))
    )
    (net (code "60") (name "Net-(C45-Pad1)") (class "Default")
      (node (ref "C45") (pin "1") (pinfunction "1_1") (pintype "passive"))
      (node (ref "J1") (pin "19") (pinfunction "19_19") (pintype "bidirectional"))
    )
    (net (code "61") (name "Net-(C46-Pad1)") (class "Default")
      (node (ref "C46") (pin "1") (pinfunction "1_1") (pintype "passive"))
      (node (ref "J1") (pin "20") (pinfunction "20_20") (pintype "bidirectional"))
    )
    (net (code "62") (name "Net-(C47-Pad1)") (class "Default")
      (node (ref "C47") (pin "1") (pinfunction "1_1") (pintype "passive"))
      (node (ref "J1") (pin "22") (pinfunction "22_22") (pintype "bidirectional"))
    )
    (net (code "63") (name "Net-(C50-Pad1)") (class "Default")
      (node (ref "C50") (pin "1") (pinfunction "1_1") (pintype "passive"))
      (node (ref "D1") (pin "C") (pinfunction "C_C") (pintype "passive"))
      (node (ref "D4") (pin "A") (pinfunction "A_A") (pintype "passive"))
    )
    (net (code "64") (name "Net-(D3-Pad-)") (class "Default")
      (node (ref "D3") (pin "-") (pinfunction "-_-") (pintype "passive"))
      (node (ref "R5") (pin "1") (pinfunction "1_1") (pintype "passive"))
    )
    (net (code "65") (name "Net-(D5-C1)") (class "Default")
      (node (ref "D5") (pin "1") (pinfunction "C1_1") (pintype "passive"))
      (node (ref "R35") (pin "1") (pinfunction "1_1") (pintype "passive"))
    )
    (net (code "66") (name "Net-(IC2-PROG)") (class "Default")
      (node (ref "IC2") (pin "5") (pinfunction "PROG_5") (pintype "input"))
      (node (ref "R3") (pin "1") (pinfunction "1_1") (pintype "passive"))
    )
    (net (code "67") (name "Net-(IC2-STAT)") (class "Default")
      (node (ref "IC2") (pin "1") (pinfunction "STAT_1") (pintype "output"))
      (node (ref "R5") (pin "2") (pinfunction "2_2") (pintype "passive"))
    )
    (net (code "68") (name "Net-(L3-2)") (class "Default")
      (node (ref "C50") (pin "2") (pinfunction "2_2") (pintype "passive"))
      (node (ref "D6") (pin "A") (pinfunction "A_A") (pintype "passive"))
      (node (ref "L3") (pin "P$2") (pinfunction "2_P$2") (pintype "passive"))
      (node (ref "Q12") (pin "3") (pinfunction "D_3") (pintype "passive"))
    )
    (net (code "69") (name "Net-(PWR-Pad-)") (class "Default")
      (node (ref "PWR") (pin "-") (pinfunction "-_-") (pintype "passive"))
      (node (ref "R1") (pin "2") (pinfunction "2_2") (pintype "passive"))
    )
    (net (code "70") (name "Net-(TF-DAT1)") (class "Default")
      (node (ref "R10") (pin "1") (pinfunction "1_1") (pintype "passive"))
      (node (ref "TF") (pin "P8") (pinfunction "DAT1_P8") (pintype "bidirectional"))
    )
    (net (code "71") (name "Net-(TF-DAT2)") (class "Default")
      (node (ref "R8") (pin "1") (pinfunction "1_1") (pintype "passive"))
      (node (ref "TF") (pin "P1") (pinfunction "DAT2_P1") (pintype "bidirectional"))
    )
    (net (code "72") (name "Net-(U3-LNA_IN)") (class "Default")
      (node (ref "C5") (pin "2") (pinfunction "2_2") (pintype "passive"))
      (node (ref "L1") (pin "2") (pinfunction "2_2") (pintype "passive"))
      (node (ref "U3") (pin "1") (pinfunction "LNA_IN_1") (pintype "bidirectional"))
    )
    (net (code "73") (name "Net-(U3-SPICLK)") (class "Default")
      (node (ref "R18") (pin "2") (pinfunction "2_2") (pintype "passive"))
      (node (ref "U3") (pin "33") (pinfunction "SPICLK_33") (pintype "bidirectional"))
    )
    (net (code "74") (name "Net-(U3-SPID)") (class "Default")
      (node (ref "R28") (pin "2") (pinfunction "2_2") (pintype "passive"))
      (node (ref "U3") (pin "35") (pinfunction "SPID_35") (pintype "bidirectional"))
    )
    (net (code "75") (name "Net-(U3-SPIHD)") (class "Default")
      (node (ref "R25") (pin "2") (pinfunction "2_2") (pintype "passive"))
      (node (ref "U3") (pin "30") (pinfunction "SPIHD_30") (pintype "bidirectional"))
    )
    (net (code "76") (name "Net-(U3-SPIQ)") (class "Default")
      (node (ref "R16") (pin "2") (pinfunction "2_2") (pintype "passive"))
      (node (ref "U3") (pin "34") (pinfunction "SPIQ_34") (pintype "bidirectional"))
    )
    (net (code "77") (name "Net-(U3-SPIWP)") (class "Default")
      (node (ref "R23") (pin "2") (pinfunction "2_2") (pintype "passive"))
      (node (ref "U3") (pin "31") (pinfunction "SPIWP_31") (pintype "bidirectional"))
    )
    (net (code "78") (name "Net-(U3-U0TXD)") (class "Default")
      (node (ref "R12") (pin "2") (pinfunction "2_2") (pintype "passive"))
      (node (ref "U3") (pin "49") (pinfunction "U0TXD_49") (pintype "bidirectional"))
    )
    (net (code "79") (name "Net-(U3-XTAL_N)") (class "Default")
      (node (ref "C13") (pin "2") (pinfunction "2_2") (pintype "passive"))
      (node (ref "U3") (pin "53") (pinfunction "XTAL_N_53") (pintype "bidirectional"))
      (node (ref "X1") (pin "3") (pinfunction "X2_3") (pintype "bidirectional"))
    )
    (net (code "80") (name "Net-(U3-XTAL_P)") (class "Default")
      (node (ref "R34") (pin "2") (pinfunction "2_2") (pintype "passive"))
      (node (ref "U3") (pin "54") (pinfunction "XTAL_P_54") (pintype "bidirectional"))
    )
    (net (code "81") (name "Net-(U5-BYP)") (class "Default")
      (node (ref "C7") (pin "2") (pinfunction "2_2") (pintype "passive"))
      (node (ref "U5") (pin "4") (pinfunction "BYP_4") (pintype "bidirectional"))
    )
    (net (code "82") (name "Net-(USB1-CC1)") (class "Default")
      (node (ref "R32") (pin "1") (pinfunction "1_1") (pintype "passive"))
      (node (ref "USB1") (pin "A5") (pinfunction "CC1_A5") (pintype "bidirectional"))
    )
    (net (code "83") (name "Net-(USB1-CC2)") (class "Default")
      (node (ref "R31") (pin "1") (pinfunction "1_1") (pintype "passive"))
      (node (ref "USB1") (pin "B5") (pinfunction "CC2_B5") (pintype "bidirectional"))
    )
    (net (code "84") (name "Net-(X1-X1)") (class "Default")
      (node (ref "C19") (pin "1") (pinfunction "1_1") (pintype "passive"))
      (node (ref "R34") (pin "1") (pinfunction "1_1") (pintype "passive"))
      (node (ref "X1") (pin "1") (pinfunction "X1_1") (pintype "bidirectional"))
    )
    (net (code "85") (name "unconnected-(J1-Pad1)") (class "Default")
      (node (ref "J1") (pin "1") (pinfunction "1_1") (pintype "bidirectional"))
    )
    (net (code "86") (name "unconnected-(J1-Pad4)") (class "Default")
      (node (ref "J1") (pin "4") (pinfunction "4_4") (pintype "bidirectional"))
    )
    (net (code "87") (name "unconnected-(J1-Pad6)") (class "Default")
      (node (ref "J1") (pin "6") (pinfunction "6_6") (pintype "bidirectional"))
    )
    (net (code "88") (name "unconnected-(J1-Pad7)") (class "Default")
      (node (ref "J1") (pin "7") (pinfunction "7_7") (pintype "bidirectional"))
    )
    (net (code "89") (name "unconnected-(TF-CD{slash}DAT3-PadP2)") (class "Default")
      (node (ref "TF") (pin "P2") (pinfunction "CD/DAT3_P2") (pintype "bidirectional"))
    )
    (net (code "90") (name "unconnected-(TF-SWITCH-PadG1)") (class "Default")
      (node (ref "TF") (pin "G1") (pinfunction "SWITCH_G1") (pintype "bidirectional"))
    )
    (net (code "91") (name "unconnected-(U3-GPIO33-Pad38)") (class "Default")
      (node (ref "U3") (pin "38") (pinfunction "GPIO33_38") (pintype "bidirectional"))
    )
    (net (code "92") (name "unconnected-(U3-GPIO34-Pad39)") (class "Default")
      (node (ref "U3") (pin "39") (pinfunction "GPIO34_39") (pintype "bidirectional"))
    )
    (net (code "93") (name "unconnected-(U3-GPIO35-Pad40)") (class "Default")
      (node (ref "U3") (pin "40") (pinfunction "GPIO35_40") (pintype "bidirectional"))
    )
    (net (code "94") (name "unconnected-(U3-GPIO36-Pad41)") (class "Default")
      (node (ref "U3") (pin "41") (pinfunction "GPIO36_41") (pintype "bidirectional"))
    )
    (net (code "95") (name "unconnected-(U3-GPIO37-Pad42)") (class "Default")
      (node (ref "U3") (pin "42") (pinfunction "GPIO37_42") (pintype "bidirectional"))
    )
    (net (code "96") (name "unconnected-(U7-CS-AUX-Pad10)") (class "Default")
      (node (ref "U7") (pin "10") (pinfunction "CS-AUX_10") (pintype "bidirectional"))
    )
    (net (code "97") (name "unconnected-(U7-INT2-Pad9)") (class "Default")
      (node (ref "U7") (pin "9") (pinfunction "INT2_9") (pintype "bidirectional"))
    )
    (net (code "98") (name "unconnected-(U7-SDO-AUX-Pad11)") (class "Default")
      (node (ref "U7") (pin "11") (pinfunction "SDO-AUX_11") (pintype "bidirectional"))
    )
  )
)
